# Connectors.net
KiCad netlist of a schematic drawn in Altium Designer
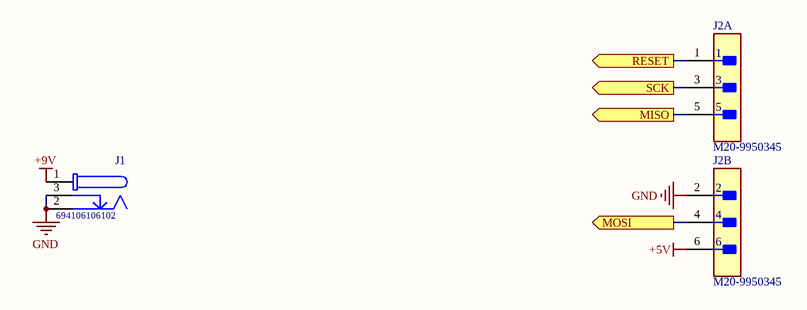
[diagram p0: Connectors.SchDoc]

(export (version "E")
  (design (tool "Eeschema 10.0.6"))
  (components
    (comp (ref "J1")
      (value "694106106102")
      (footprint "694106106102")
      (description "DC Power Jack Connector with 4 soldering pads & Pegs WR-DC, Male, Right Angled, SMT, 5 A, 24 V")
      (fields (field (name "MANUFACTURER") "Wurth Elektronik") (field (name "PUBLISHER") "WurthElektronik"))
      (libsource (lib "Altium Content Vault") (part "WE-JACK-2CD3-RN"))
    )
    (comp (ref "J2")
      (value "M20-9950345")
      (footprint "FP-M20-9950345-MFG")
      (description "CONN HEADER R/A 6POS 2.54MM")
      (fields
        (field (name "OCTOPART") "https://octopart.com/m20-9950345-harwin-21265213")
        (field (name "MANUFACTURER") "Harwin")
      )
      (libsource (lib "Altium Content Vault") (part "b76336891f9c52daa0497ceff74f613"))
    )
  )
  (nets
    (net (code "1") (name "+5V") (class "Default")
      (node (ref "J2") (pin "6") (pinfunction "6_6") (pintype "passive"))
    )
    (net (code "2") (name "+9V") (class "Default")
      (node (ref "J1") (pin "1") (pinfunction "1_1") (pintype "passive"))
    )
    (net (code "3") (name "/MISO") (class "Default")
      (node (ref "J2") (pin "5") (pinfunction "5_5") (pintype "passive"))
    )
    (net (code "4") (name "/MOSI") (class "Default")
      (node (ref "J2") (pin "4") (pinfunction "4_4") (pintype "passive"))
    )
    (net (code "5") (name "/RESET") (class "Default")
      (node (ref "J2") (pin "1") (pinfunction "1_1") (pintype "passive"))
    )
    (net (code "6") (name "/SCK") (class "Default")
      (node (ref "J2") (pin "3") (pinfunction "3_3") (pintype "passive"))
    )
    (net (code "7") (name "GND") (class "Default")
      (node (ref "J1") (pin "2") (pinfunction "2_2") (pintype "passive"))
      (node (ref "J1") (pin "3") (pinfunction "3_3") (pintype "passive"))
      (node (ref "J2") (pin "2") (pinfunction "2_2") (pintype "passive"))
    )
  )
)
